# untitled.net
KiCad netlist of a schematic drawn in EAGLE
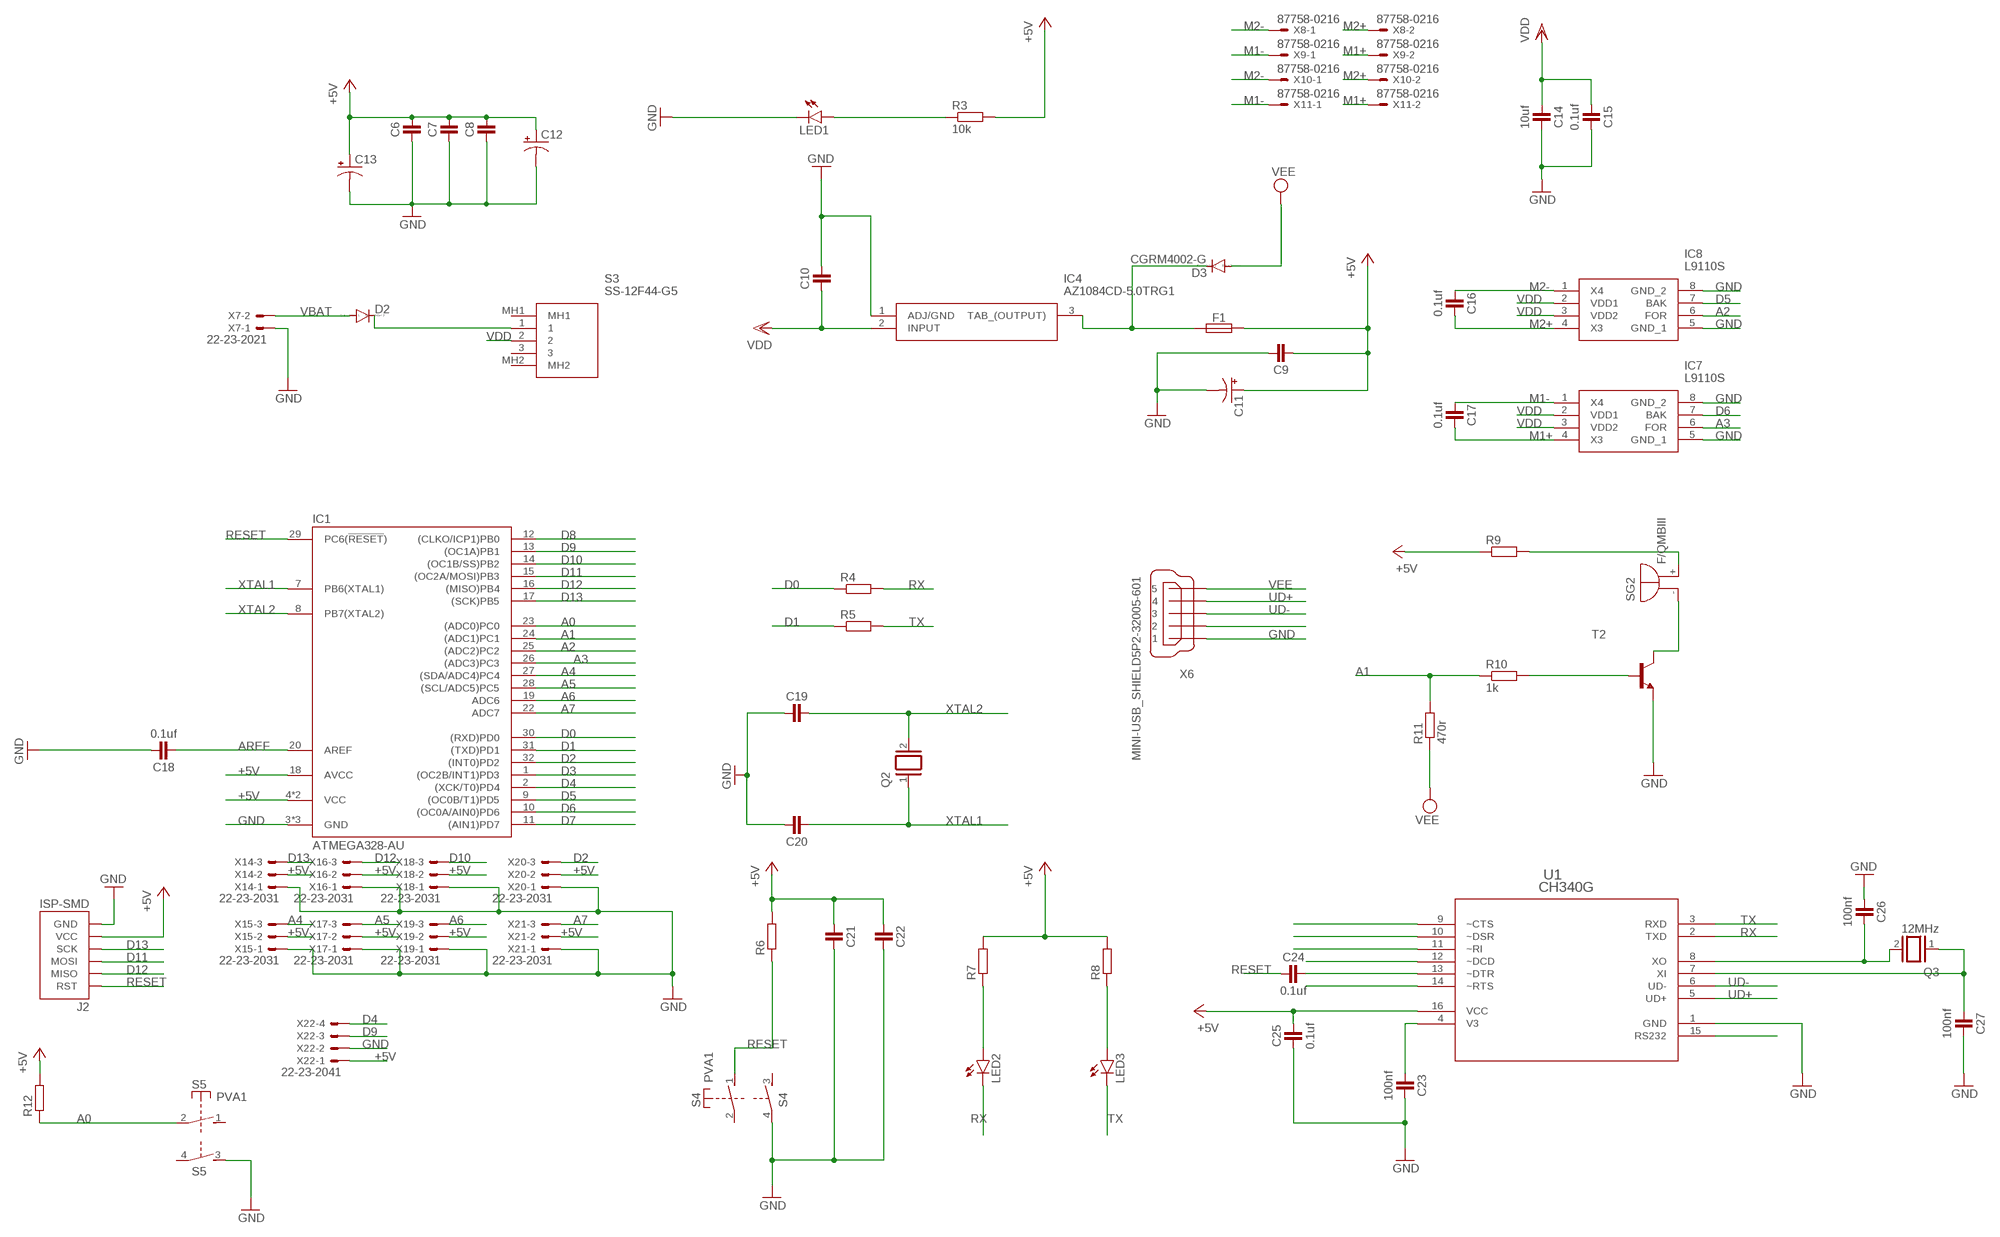
[diagram p0: schematic, sheet 1]

(export (version "E")
  (design (tool "Eeschema 10.0.6"))
  (components
    (comp (ref "C6")
      (value "CAPACITOR-0603")
      (footprint "eagle-import:C0603")
      (libsource (lib "eagle-import") (part "CAPACITOR-0603"))
    )
    (comp (ref "C7")
      (value "CAPACITOR-0603")
      (footprint "eagle-import:C0603")
      (libsource (lib "eagle-import") (part "CAPACITOR-0603"))
    )
    (comp (ref "C8")
      (value "CAPACITOR-0603")
      (footprint "eagle-import:C0603")
      (libsource (lib "eagle-import") (part "CAPACITOR-0603"))
    )
    (comp (ref "C9")
      (value "CAPACITOR-0603")
      (footprint "eagle-import:C0603")
      (libsource (lib "eagle-import") (part "CAPACITOR-0603"))
    )
    (comp (ref "C10")
      (value "CAPACITOR-0603")
      (footprint "eagle-import:C0603")
      (libsource (lib "eagle-import") (part "CAPACITOR-0603"))
    )
    (comp (ref "C11")
      (value "CPOL-USB/3528-21R")
      (footprint "eagle-import:B_3528-21R")
      (libsource (lib "eagle-import") (part "CPOL-USB/3528-21R"))
    )
    (comp (ref "C12")
      (value "CPOL-USB/3528-21R")
      (footprint "eagle-import:B_3528-21R")
      (libsource (lib "eagle-import") (part "CPOL-USB/3528-21R"))
    )
    (comp (ref "C13")
      (value "CPOL-USB/3528-21R")
      (footprint "eagle-import:B_3528-21R")
      (libsource (lib "eagle-import") (part "CPOL-USB/3528-21R"))
    )
    (comp (ref "C14")
      (value "10uf")
      (footprint "eagle-import:C0603")
      (libsource (lib "eagle-import") (part "CAPACITOR-0603"))
    )
    (comp (ref "C15")
      (value "0.1uf")
      (footprint "eagle-import:C0603")
      (libsource (lib "eagle-import") (part "CAPACITOR-0603"))
    )
    (comp (ref "C16")
      (value "0.1uf")
      (footprint "eagle-import:C0603")
      (libsource (lib "eagle-import") (part "CAPACITOR-0603"))
    )
    (comp (ref "C17")
      (value "0.1uf")
      (footprint "eagle-import:C0603")
      (libsource (lib "eagle-import") (part "CAPACITOR-0603"))
    )
    (comp (ref "C18")
      (value "0.1uf")
      (footprint "eagle-import:C0603")
      (libsource (lib "eagle-import") (part "CAPACITOR-0603"))
    )
    (comp (ref "C19")
      (value "CAPACITOR-0603")
      (footprint "eagle-import:C0603")
      (libsource (lib "eagle-import") (part "CAPACITOR-0603"))
    )
    (comp (ref "C20")
      (value "CAPACITOR-0603")
      (footprint "eagle-import:C0603")
      (libsource (lib "eagle-import") (part "CAPACITOR-0603"))
    )
    (comp (ref "C21")
      (value "CAPACITOR-0603")
      (footprint "eagle-import:C0603")
      (libsource (lib "eagle-import") (part "CAPACITOR-0603"))
    )
    (comp (ref "C22")
      (value "CAPACITOR-0603")
      (footprint "eagle-import:C0603")
      (libsource (lib "eagle-import") (part "CAPACITOR-0603"))
    )
    (comp (ref "C23")
      (value "100nf")
      (footprint "eagle-import:C0603")
      (libsource (lib "eagle-import") (part "CAPACITOR-0603"))
    )
    (comp (ref "C24")
      (value "0.1uf")
      (footprint "eagle-import:C0603")
      (libsource (lib "eagle-import") (part "CAPACITOR-0603"))
    )
    (comp (ref "C25")
      (value "0.1uf")
      (footprint "eagle-import:C0603")
      (libsource (lib "eagle-import") (part "CAPACITOR-0603"))
    )
    (comp (ref "C26")
      (value "100nf")
      (footprint "eagle-import:C0603")
      (libsource (lib "eagle-import") (part "CAPACITOR-0603"))
    )
    (comp (ref "C27")
      (value "100nf")
      (footprint "eagle-import:C0603")
      (libsource (lib "eagle-import") (part "CAPACITOR-0603"))
    )
    (comp (ref "D2")
      (value "DIODE-DO-214AC")
      (footprint "eagle-import:DO-214AC")
      (libsource (lib "eagle-import") (part "DIODE-DO-214AC"))
    )
    (comp (ref "D3")
      (value "CGRM4002-G")
      (footprint "eagle-import:SOD-123_MINI-SMA")
      (libsource (lib "eagle-import") (part "CGRM400-G2"))
    )
    (comp (ref "F1")
      (value "FUSE-1812")
      (footprint "eagle-import:C1812")
      (libsource (lib "eagle-import") (part "FUSE-1812"))
    )
    (comp (ref "IC1")
      (value "ATMEGA328-AU")
      (footprint "eagle-import:TQFP32")
      (libsource (lib "eagle-import") (part "ATMEGA328-AU"))
    )
    (comp (ref "IC4")
      (value "AZ1084CD-5.0TRG1")
      (footprint "eagle-import:TO-252_1")
      (fields (field (name "MOUSER_PART_NUMBER") "621-AZ1084CD-5.0TRG1"))
      (libsource (lib "eagle-import") (part "AZ1084CD-5.0TRG1"))
    )
    (comp (ref "IC7")
      (value "L9110S")
      (footprint "eagle-import:SOIC127P600X175-8N")
      (libsource (lib "eagle-import") (part "L9110S"))
    )
    (comp (ref "IC8")
      (value "L9110S")
      (footprint "eagle-import:SOIC127P600X175-8N")
      (libsource (lib "eagle-import") (part "L9110S"))
    )
    (comp (ref "J2")
      (value "ISP-SMD")
      (footprint "eagle-import:ISP-2X3_SMD")
      (libsource (lib "eagle-import") (part "ISP-SMD"))
    )
    (comp (ref "LED1")
      (value "LEDCHIPLED_0805")
      (footprint "eagle-import:CHIPLED_0805")
      (libsource (lib "eagle-import") (part "LEDCHIPLED_0805"))
    )
    (comp (ref "LED2")
      (value "LEDCHIPLED_0805")
      (footprint "eagle-import:CHIPLED_0805")
      (libsource (lib "eagle-import") (part "LEDCHIPLED_0805"))
    )
    (comp (ref "LED3")
      (value "LEDCHIPLED_0805")
      (footprint "eagle-import:CHIPLED_0805")
      (libsource (lib "eagle-import") (part "LEDCHIPLED_0805"))
    )
    (comp (ref "Q2")
      (value "XTAL/S")
      (footprint "eagle-import:QS")
      (libsource (lib "eagle-import") (part "XTAL/S"))
    )
    (comp (ref "Q3")
      (value "12MHz")
      (footprint "eagle-import:QS")
      (libsource (lib "eagle-import") (part "XTAL/S"))
    )
    (comp (ref "R3")
      (value "10k")
      (footprint "eagle-import:R0603")
      (libsource (lib "eagle-import") (part "R-EU_R0603"))
    )
    (comp (ref "R4")
      (value "R-EU_R0603")
      (footprint "eagle-import:R0603")
      (libsource (lib "eagle-import") (part "R-EU_R0603"))
    )
    (comp (ref "R5")
      (value "R-EU_R0603")
      (footprint "eagle-import:R0603")
      (libsource (lib "eagle-import") (part "R-EU_R0603"))
    )
    (comp (ref "R6")
      (value "R-EU_R0603")
      (footprint "eagle-import:R0603")
      (libsource (lib "eagle-import") (part "R-EU_R0603"))
    )
    (comp (ref "R7")
      (value "R-EU_R0603")
      (footprint "eagle-import:R0603")
      (libsource (lib "eagle-import") (part "R-EU_R0603"))
    )
    (comp (ref "R8")
      (value "R-EU_R0603")
      (footprint "eagle-import:R0603")
      (libsource (lib "eagle-import") (part "R-EU_R0603"))
    )
    (comp (ref "R9")
      (value "R-EU_R0603")
      (footprint "eagle-import:R0603")
      (libsource (lib "eagle-import") (part "R-EU_R0603"))
    )
    (comp (ref "R10")
      (value "1k")
      (footprint "eagle-import:R0603")
      (libsource (lib "eagle-import") (part "R-EU_R0603"))
    )
    (comp (ref "R11")
      (value "470r")
      (footprint "eagle-import:R0603")
      (libsource (lib "eagle-import") (part "R-EU_R0603"))
    )
    (comp (ref "R12")
      (value "R-EU_R0603")
      (footprint "eagle-import:R0603")
      (libsource (lib "eagle-import") (part "R-EU_R0603"))
    )
    (comp (ref "S3")
      (value "SS-12F44-G5")
      (footprint "eagle-import:SS12F44G5")
      (libsource (lib "eagle-import") (part "SS-12F44-G5"))
    )
    (comp (ref "S4")
      (value "PVA1")
      (footprint "eagle-import:PVA1F")
      (libsource (lib "eagle-import") (part "PVA1"))
    )
    (comp (ref "S5")
      (value "PVA1")
      (footprint "eagle-import:PVA1F")
      (libsource (lib "eagle-import") (part "PVA1"))
    )
    (comp (ref "SG2")
      (value "F/QMBIII")
      (footprint "eagle-import:F_QMBIII")
      (libsource (lib "eagle-import") (part "F/QMBIII"))
    )
    (comp (ref "T2")
      (value "BC817-NPN-SOT23-BEC")
      (footprint "eagle-import:SOT23-BEC")
      (libsource (lib "eagle-import") (part "-NPN-SOT23-BECBC817"))
    )
    (comp (ref "U1")
      (value "CH340G")
      (footprint "eagle-import:SOP16-50-062A")
      (fields (field (name "DESIGNER") "CHIPHOME"))
      (libsource (lib "eagle-import") (part "CH340G"))
    )
    (comp (ref "X6")
      (value "MINI-USB_SHIELD5P2-32005-601")
      (footprint "eagle-import:32005-601")
      (libsource (lib "eagle-import") (part "MINI-USB_SHIELD5P2-32005-601"))
    )
    (comp (ref "X7")
      (value "22-23-2021")
      (footprint "eagle-import:22-23-2021")
      (fields (field (name "MF") "MOLEX"))
      (libsource (lib "eagle-import") (part "22-23-2021"))
    )
    (comp (ref "X8")
      (value "87758-0216")
      (footprint "eagle-import:87758-0216")
      (fields (field (name "MF") "MOLEX"))
      (libsource (lib "eagle-import") (part "87758-0216"))
    )
    (comp (ref "X9")
      (value "87758-0216")
      (footprint "eagle-import:87758-0216")
      (fields (field (name "MF") "MOLEX"))
      (libsource (lib "eagle-import") (part "87758-0216"))
    )
    (comp (ref "X10")
      (value "87758-0216")
      (footprint "eagle-import:87758-0216")
      (fields (field (name "MF") "MOLEX"))
      (libsource (lib "eagle-import") (part "87758-0216"))
    )
    (comp (ref "X11")
      (value "87758-0216")
      (footprint "eagle-import:87758-0216")
      (fields (field (name "MF") "MOLEX"))
      (libsource (lib "eagle-import") (part "87758-0216"))
    )
    (comp (ref "X14")
      (value "22-23-2031")
      (footprint "eagle-import:22-23-2031")
      (fields (field (name "MF") "MOLEX"))
      (libsource (lib "eagle-import") (part "22-23-2031"))
    )
    (comp (ref "X15")
      (value "22-23-2031")
      (footprint "eagle-import:22-23-2031")
      (fields (field (name "MF") "MOLEX"))
      (libsource (lib "eagle-import") (part "22-23-2031"))
    )
    (comp (ref "X16")
      (value "22-23-2031")
      (footprint "eagle-import:22-23-2031")
      (fields (field (name "MF") "MOLEX"))
      (libsource (lib "eagle-import") (part "22-23-2031"))
    )
    (comp (ref "X17")
      (value "22-23-2031")
      (footprint "eagle-import:22-23-2031")
      (fields (field (name "MF") "MOLEX"))
      (libsource (lib "eagle-import") (part "22-23-2031"))
    )
    (comp (ref "X18")
      (value "22-23-2031")
      (footprint "eagle-import:22-23-2031")
      (fields (field (name "MF") "MOLEX"))
      (libsource (lib "eagle-import") (part "22-23-2031"))
    )
    (comp (ref "X19")
      (value "22-23-2031")
      (footprint "eagle-import:22-23-2031")
      (fields (field (name "MF") "MOLEX"))
      (libsource (lib "eagle-import") (part "22-23-2031"))
    )
    (comp (ref "X20")
      (value "22-23-2031")
      (footprint "eagle-import:22-23-2031")
      (fields (field (name "MF") "MOLEX"))
      (libsource (lib "eagle-import") (part "22-23-2031"))
    )
    (comp (ref "X21")
      (value "22-23-2031")
      (footprint "eagle-import:22-23-2031")
      (fields (field (name "MF") "MOLEX"))
      (libsource (lib "eagle-import") (part "22-23-2031"))
    )
    (comp (ref "X22")
      (value "22-23-2041")
      (footprint "eagle-import:22-23-2041")
      (fields (field (name "MF") "MOLEX"))
      (libsource (lib "eagle-import") (part "22-23-2041"))
    )
  )
  (nets
    (net (code "1") (name "+5V") (class "Default")
      (node (ref "C11") (pin "+") (pinfunction "+_+") (pintype "passive"))
      (node (ref "C12") (pin "+") (pinfunction "+_+") (pintype "passive"))
      (node (ref "C13") (pin "+") (pinfunction "+_+") (pintype "passive"))
      (node (ref "C21") (pin "1") (pinfunction "1_1") (pintype "passive"))
      (node (ref "C22") (pin "1") (pinfunction "1_1") (pintype "passive"))
      (node (ref "C25") (pin "2") (pinfunction "2_2") (pintype "passive"))
      (node (ref "C6") (pin "2") (pinfunction "2_2") (pintype "passive"))
      (node (ref "C7") (pin "2") (pinfunction "2_2") (pintype "passive"))
      (node (ref "C8") (pin "2") (pinfunction "2_2") (pintype "passive"))
      (node (ref "C9") (pin "1") (pinfunction "1_1") (pintype "passive"))
      (node (ref "F1") (pin "2") (pinfunction "2_2") (pintype "passive"))
      (node (ref "IC1") (pin "18") (pinfunction "AVCC_18") (pintype "power_in"))
      (node (ref "IC1") (pin "4") (pinfunction "VCC_4") (pintype "power_in"))
      (node (ref "IC1") (pin "6") (pinfunction "VCC_6") (pintype "power_in"))
      (node (ref "J2") (pin "VCC") (pinfunction "VCC_VCC") (pintype "power_in"))
      (node (ref "R12") (pin "2") (pinfunction "2_2") (pintype "passive"))
      (node (ref "R3") (pin "2") (pinfunction "2_2") (pintype "passive"))
      (node (ref "R6") (pin "2") (pinfunction "2_2") (pintype "passive"))
      (node (ref "R7") (pin "2") (pinfunction "2_2") (pintype "passive"))
      (node (ref "R8") (pin "2") (pinfunction "2_2") (pintype "passive"))
      (node (ref "R9") (pin "1") (pinfunction "1_1") (pintype "passive"))
      (node (ref "U1") (pin "16") (pinfunction "VCC_16") (pintype "passive"))
      (node (ref "X14") (pin "2") (pinfunction "S_2") (pintype "passive"))
      (node (ref "X15") (pin "2") (pinfunction "S_2") (pintype "passive"))
      (node (ref "X16") (pin "2") (pinfunction "S_2") (pintype "passive"))
      (node (ref "X17") (pin "2") (pinfunction "S_2") (pintype "passive"))
      (node (ref "X18") (pin "2") (pinfunction "S_2") (pintype "passive"))
      (node (ref "X19") (pin "2") (pinfunction "S_2") (pintype "passive"))
      (node (ref "X20") (pin "2") (pinfunction "S_2") (pintype "passive"))
      (node (ref "X21") (pin "2") (pinfunction "S_2") (pintype "passive"))
      (node (ref "X22") (pin "1") (pinfunction "S_1") (pintype "passive"))
    )
    (net (code "2") (name "/A0") (class "Default")
      (node (ref "IC1") (pin "23") (pinfunction "(ADC0)PC0_23") (pintype "bidirectional"))
      (node (ref "R12") (pin "1") (pinfunction "1_1") (pintype "passive"))
      (node (ref "S5") (pin "2") (pinfunction "P_2") (pintype "passive"))
    )
    (net (code "3") (name "/A1") (class "Default")
      (node (ref "IC1") (pin "24") (pinfunction "(ADC1)PC1_24") (pintype "bidirectional"))
      (node (ref "R10") (pin "1") (pinfunction "1_1") (pintype "passive"))
      (node (ref "R11") (pin "2") (pinfunction "2_2") (pintype "passive"))
    )
    (net (code "4") (name "/A2") (class "Default")
      (node (ref "IC1") (pin "25") (pinfunction "(ADC2)PC2_25") (pintype "bidirectional"))
      (node (ref "IC8") (pin "6") (pinfunction "FOR_6") (pintype "bidirectional"))
    )
    (net (code "5") (name "/A3") (class "Default")
      (node (ref "IC1") (pin "26") (pinfunction "(ADC3)PC3_26") (pintype "bidirectional"))
      (node (ref "IC7") (pin "6") (pinfunction "FOR_6") (pintype "bidirectional"))
    )
    (net (code "6") (name "/A4") (class "Default")
      (node (ref "IC1") (pin "27") (pinfunction "(SDA/ADC4)PC4_27") (pintype "bidirectional"))
      (node (ref "X15") (pin "3") (pinfunction "S_3") (pintype "passive"))
    )
    (net (code "7") (name "/A5") (class "Default")
      (node (ref "IC1") (pin "28") (pinfunction "(SCL/ADC5)PC5_28") (pintype "bidirectional"))
      (node (ref "X17") (pin "3") (pinfunction "S_3") (pintype "passive"))
    )
    (net (code "8") (name "/A6") (class "Default")
      (node (ref "IC1") (pin "19") (pinfunction "ADC6_19") (pintype "bidirectional"))
      (node (ref "X19") (pin "3") (pinfunction "S_3") (pintype "passive"))
    )
    (net (code "9") (name "/A7") (class "Default")
      (node (ref "IC1") (pin "22") (pinfunction "ADC7_22") (pintype "bidirectional"))
      (node (ref "X21") (pin "3") (pinfunction "S_3") (pintype "passive"))
    )
    (net (code "10") (name "/AREF") (class "Default")
      (node (ref "C18") (pin "1") (pinfunction "1_1") (pintype "passive"))
      (node (ref "IC1") (pin "20") (pinfunction "AREF_20") (pintype "passive"))
    )
    (net (code "11") (name "/D0") (class "Default")
      (node (ref "IC1") (pin "30") (pinfunction "(RXD)PD0_30") (pintype "bidirectional"))
      (node (ref "R4") (pin "1") (pinfunction "1_1") (pintype "passive"))
    )
    (net (code "12") (name "/D1") (class "Default")
      (node (ref "IC1") (pin "31") (pinfunction "(TXD)PD1_31") (pintype "bidirectional"))
      (node (ref "R5") (pin "1") (pinfunction "1_1") (pintype "passive"))
    )
    (net (code "13") (name "/D2") (class "Default")
      (node (ref "IC1") (pin "32") (pinfunction "(INT0)PD2_32") (pintype "bidirectional"))
      (node (ref "X20") (pin "3") (pinfunction "S_3") (pintype "passive"))
    )
    (net (code "14") (name "/D3") (class "Default")
      (node (ref "IC1") (pin "1") (pinfunction "(OC2B/INT1)PD3_1") (pintype "bidirectional"))
    )
    (net (code "15") (name "/D4") (class "Default")
      (node (ref "IC1") (pin "2") (pinfunction "(XCK/T0)PD4_2") (pintype "bidirectional"))
      (node (ref "X22") (pin "4") (pinfunction "S_4") (pintype "passive"))
    )
    (net (code "16") (name "/D5") (class "Default")
      (node (ref "IC1") (pin "9") (pinfunction "(OC0B/T1)PD5_9") (pintype "bidirectional"))
      (node (ref "IC8") (pin "7") (pinfunction "BAK_7") (pintype "bidirectional"))
    )
    (net (code "17") (name "/D6") (class "Default")
      (node (ref "IC1") (pin "10") (pinfunction "(OC0A/AIN0)PD6_10") (pintype "bidirectional"))
      (node (ref "IC7") (pin "7") (pinfunction "BAK_7") (pintype "bidirectional"))
    )
    (net (code "18") (name "/D7") (class "Default")
      (node (ref "IC1") (pin "11") (pinfunction "(AIN1)PD7_11") (pintype "bidirectional"))
    )
    (net (code "19") (name "/D8") (class "Default")
      (node (ref "IC1") (pin "12") (pinfunction "(CLKO/ICP1)PB0_12") (pintype "bidirectional"))
    )
    (net (code "20") (name "/D9") (class "Default")
      (node (ref "IC1") (pin "13") (pinfunction "(OC1A)PB1_13") (pintype "bidirectional"))
      (node (ref "X22") (pin "3") (pinfunction "S_3") (pintype "passive"))
    )
    (net (code "21") (name "/D10") (class "Default")
      (node (ref "IC1") (pin "14") (pinfunction "(OC1B/SS)PB2_14") (pintype "bidirectional"))
      (node (ref "X18") (pin "3") (pinfunction "S_3") (pintype "passive"))
    )
    (net (code "22") (name "/D11") (class "Default")
      (node (ref "IC1") (pin "15") (pinfunction "(OC2A/MOSI)PB3_15") (pintype "bidirectional"))
      (node (ref "J2") (pin "MOSI") (pinfunction "MOSI_MOSI") (pintype "bidirectional"))
    )
    (net (code "23") (name "/D12") (class "Default")
      (node (ref "IC1") (pin "16") (pinfunction "(MISO)PB4_16") (pintype "bidirectional"))
      (node (ref "J2") (pin "MISO") (pinfunction "MISO_MISO") (pintype "bidirectional"))
      (node (ref "X16") (pin "3") (pinfunction "S_3") (pintype "passive"))
    )
    (net (code "24") (name "/D13") (class "Default")
      (node (ref "IC1") (pin "17") (pinfunction "(SCK)PB5_17") (pintype "bidirectional"))
      (node (ref "J2") (pin "SCK") (pinfunction "SCK_SCK") (pintype "bidirectional"))
      (node (ref "X14") (pin "3") (pinfunction "S_3") (pintype "passive"))
    )
    (net (code "25") (name "/M1+") (class "Default")
      (node (ref "C17") (pin "2") (pinfunction "2_2") (pintype "passive"))
      (node (ref "IC7") (pin "4") (pinfunction "X3_4") (pintype "bidirectional"))
      (node (ref "X11") (pin "2") (pinfunction "S_2") (pintype "passive"))
      (node (ref "X9") (pin "2") (pinfunction "S_2") (pintype "passive"))
    )
    (net (code "26") (name "/M1-") (class "Default")
      (node (ref "C17") (pin "1") (pinfunction "1_1") (pintype "passive"))
      (node (ref "IC7") (pin "1") (pinfunction "X4_1") (pintype "bidirectional"))
      (node (ref "X11") (pin "1") (pinfunction "S_1") (pintype "passive"))
      (node (ref "X9") (pin "1") (pinfunction "S_1") (pintype "passive"))
    )
    (net (code "27") (name "/M2+") (class "Default")
      (node (ref "C16") (pin "2") (pinfunction "2_2") (pintype "passive"))
      (node (ref "IC8") (pin "4") (pinfunction "X3_4") (pintype "bidirectional"))
      (node (ref "X10") (pin "2") (pinfunction "S_2") (pintype "passive"))
      (node (ref "X8") (pin "2") (pinfunction "S_2") (pintype "passive"))
    )
    (net (code "28") (name "/M2-") (class "Default")
      (node (ref "C16") (pin "1") (pinfunction "1_1") (pintype "passive"))
      (node (ref "IC8") (pin "1") (pinfunction "X4_1") (pintype "bidirectional"))
      (node (ref "X10") (pin "1") (pinfunction "S_1") (pintype "passive"))
      (node (ref "X8") (pin "1") (pinfunction "S_1") (pintype "passive"))
    )
    (net (code "29") (name "/RESET") (class "Default")
      (node (ref "C24") (pin "1") (pinfunction "1_1") (pintype "passive"))
      (node (ref "IC1") (pin "29") (pinfunction "PC6(~{RESET})_29") (pintype "bidirectional"))
      (node (ref "J2") (pin "RST") (pinfunction "RST_RST") (pintype "bidirectional"))
      (node (ref "R6") (pin "1") (pinfunction "1_1") (pintype "passive"))
      (node (ref "S4") (pin "1") (pinfunction "S_1") (pintype "passive"))
    )
    (net (code "30") (name "/RX") (class "Default")
      (node (ref "LED2") (pin "C") (pinfunction "C_C") (pintype "passive"))
      (node (ref "R4") (pin "2") (pinfunction "2_2") (pintype "passive"))
      (node (ref "U1") (pin "2") (pinfunction "TXD_2") (pintype "passive"))
    )
    (net (code "31") (name "/TX") (class "Default")
      (node (ref "LED3") (pin "C") (pinfunction "C_C") (pintype "passive"))
      (node (ref "R5") (pin "2") (pinfunction "2_2") (pintype "passive"))
      (node (ref "U1") (pin "3") (pinfunction "RXD_3") (pintype "passive"))
    )
    (net (code "32") (name "/UD+") (class "Default")
      (node (ref "U1") (pin "5") (pinfunction "UD+_5") (pintype "passive"))
      (node (ref "X6") (pin "4") (pinfunction "4_4") (pintype "passive"))
    )
    (net (code "33") (name "/UD-") (class "Default")
      (node (ref "U1") (pin "6") (pinfunction "UD-_6") (pintype "passive"))
      (node (ref "X6") (pin "3") (pinfunction "3_3") (pintype "passive"))
    )
    (net (code "34") (name "/VBAT") (class "Default")
      (node (ref "D2") (pin "A") (pinfunction "A_A") (pintype "passive"))
      (node (ref "X7") (pin "2") (pinfunction "S_2") (pintype "passive"))
    )
    (net (code "35") (name "/XTAL1") (class "Default")
      (node (ref "C20") (pin "1") (pinfunction "1_1") (pintype "passive"))
      (node (ref "IC1") (pin "7") (pinfunction "PB6(XTAL1)_7") (pintype "bidirectional"))
      (node (ref "Q2") (pin "1") (pinfunction "1_1") (pintype "passive"))
    )
    (net (code "36") (name "/XTAL2") (class "Default")
      (node (ref "C19") (pin "2") (pinfunction "2_2") (pintype "passive"))
      (node (ref "IC1") (pin "8") (pinfunction "PB7(XTAL2)_8") (pintype "bidirectional"))
      (node (ref "Q2") (pin "2") (pinfunction "2_2") (pintype "passive"))
    )
    (net (code "37") (name "GND") (class "Default")
      (node (ref "C10") (pin "2") (pinfunction "2_2") (pintype "passive"))
      (node (ref "C11") (pin "-") (pinfunction "-_-") (pintype "passive"))
      (node (ref "C12") (pin "-") (pinfunction "-_-") (pintype "passive"))
      (node (ref "C13") (pin "-") (pinfunction "-_-") (pintype "passive"))
      (node (ref "C14") (pin "2") (pinfunction "2_2") (pintype "passive"))
      (node (ref "C15") (pin "2") (pinfunction "2_2") (pintype "passive"))
      (node (ref "C18") (pin "2") (pinfunction "2_2") (pintype "passive"))
      (node (ref "C19") (pin "1") (pinfunction "1_1") (pintype "passive"))
      (node (ref "C20") (pin "2") (pinfunction "2_2") (pintype "passive"))
      (node (ref "C21") (pin "2") (pinfunction "2_2") (pintype "passive"))
      (node (ref "C22") (pin "2") (pinfunction "2_2") (pintype "passive"))
      (node (ref "C23") (pin "2") (pinfunction "2_2") (pintype "passive"))
      (node (ref "C25") (pin "1") (pinfunction "1_1") (pintype "passive"))
      (node (ref "C26") (pin "1") (pinfunction "1_1") (pintype "passive"))
      (node (ref "C27") (pin "2") (pinfunction "2_2") (pintype "passive"))
      (node (ref "C6") (pin "1") (pinfunction "1_1") (pintype "passive"))
      (node (ref "C7") (pin "1") (pinfunction "1_1") (pintype "passive"))
      (node (ref "C8") (pin "1") (pinfunction "1_1") (pintype "passive"))
      (node (ref "C9") (pin "2") (pinfunction "2_2") (pintype "passive"))
      (node (ref "IC1") (pin "21") (pinfunction "GND_21") (pintype "power_in"))
      (node (ref "IC1") (pin "3") (pinfunction "GND_3") (pintype "power_in"))
      (node (ref "IC1") (pin "5") (pinfunction "GND_5") (pintype "power_in"))
      (node (ref "IC4") (pin "1") (pinfunction "ADJ/GND_1") (pintype "bidirectional"))
      (node (ref "IC7") (pin "5") (pinfunction "GND_1_5") (pintype "bidirectional"))
      (node (ref "IC7") (pin "8") (pinfunction "GND_2_8") (pintype "bidirectional"))
      (node (ref "IC8") (pin "5") (pinfunction "GND_1_5") (pintype "bidirectional"))
      (node (ref "IC8") (pin "8") (pinfunction "GND_2_8") (pintype "bidirectional"))
      (node (ref "J2") (pin "GND") (pinfunction "GND_GND") (pintype "power_in"))
      (node (ref "LED1") (pin "C") (pinfunction "C_C") (pintype "passive"))
      (node (ref "S4") (pin "4") (pinfunction "P_4") (pintype "passive"))
      (node (ref "S5") (pin "3") (pinfunction "S_3") (pintype "passive"))
      (node (ref "T2") (pin "E") (pinfunction "E_E") (pintype "passive"))
      (node (ref "U1") (pin "1") (pinfunction "GND_1") (pintype "passive"))
      (node (ref "X14") (pin "1") (pinfunction "S_1") (pintype "passive"))
      (node (ref "X15") (pin "1") (pinfunction "S_1") (pintype "passive"))
      (node (ref "X16") (pin "1") (pinfunction "S_1") (pintype "passive"))
      (node (ref "X17") (pin "1") (pinfunction "S_1") (pintype "passive"))
      (node (ref "X18") (pin "1") (pinfunction "S_1") (pintype "passive"))
      (node (ref "X19") (pin "1") (pinfunction "S_1") (pintype "passive"))
      (node (ref "X20") (pin "1") (pinfunction "S_1") (pintype "passive"))
      (node (ref "X21") (pin "1") (pinfunction "S_1") (pintype "passive"))
      (node (ref "X22") (pin "2") (pinfunction "S_2") (pintype "passive"))
      (node (ref "X6") (pin "1") (pinfunction "1_1") (pintype "passive"))
      (node (ref "X7") (pin "1") (pinfunction "S_1") (pintype "passive"))
    )
    (net (code "38") (name "Net-(D2-PadC)") (class "Default")
      (node (ref "D2") (pin "C") (pinfunction "C_C") (pintype "passive"))
      (node (ref "S3") (pin "1") (pinfunction "1_1") (pintype "bidirectional"))
    )
    (net (code "39") (name "Net-(IC4-TAB_(OUTPUT))") (class "Default")
      (node (ref "D3") (pin "C") (pinfunction "C_C") (pintype "passive"))
      (node (ref "F1") (pin "1") (pinfunction "1_1") (pintype "passive"))
      (node (ref "IC4") (pin "3") (pinfunction "TAB_(OUTPUT)_3") (pintype "bidirectional"))
    )
    (net (code "40") (name "Net-(LED1-PadA)") (class "Default")
      (node (ref "LED1") (pin "A") (pinfunction "A_A") (pintype "passive"))
      (node (ref "R3") (pin "1") (pinfunction "1_1") (pintype "passive"))
    )
    (net (code "41") (name "Net-(LED2-PadA)") (class "Default")
      (node (ref "LED2") (pin "A") (pinfunction "A_A") (pintype "passive"))
      (node (ref "R7") (pin "1") (pinfunction "1_1") (pintype "passive"))
    )
    (net (code "42") (name "Net-(LED3-PadA)") (class "Default")
      (node (ref "LED3") (pin "A") (pinfunction "A_A") (pintype "passive"))
      (node (ref "R8") (pin "1") (pinfunction "1_1") (pintype "passive"))
    )
    (net (code "43") (name "Net-(R10-Pad2)") (class "Default")
      (node (ref "R10") (pin "2") (pinfunction "2_2") (pintype "passive"))
      (node (ref "T2") (pin "B") (pinfunction "B_B") (pintype "passive"))
    )
    (net (code "44") (name "Net-(SG2-+)") (class "Default")
      (node (ref "SG2") (pin "-") (pinfunction "+_-") (pintype "passive"))
      (node (ref "T2") (pin "C") (pinfunction "C_C") (pintype "passive"))
    )
    (net (code "45") (name "Net-(SG2--)") (class "Default")
      (node (ref "R9") (pin "2") (pinfunction "2_2") (pintype "passive"))
      (node (ref "SG2") (pin "+") (pinfunction "-_+") (pintype "passive"))
    )
    (net (code "46") (name "Net-(U1-V3)") (class "Default")
      (node (ref "C23") (pin "1") (pinfunction "1_1") (pintype "passive"))
      (node (ref "U1") (pin "4") (pinfunction "V3_4") (pintype "passive"))
    )
    (net (code "47") (name "Net-(U1-XI)") (class "Default")
      (node (ref "C27") (pin "1") (pinfunction "1_1") (pintype "passive"))
      (node (ref "Q3") (pin "1") (pinfunction "1_1") (pintype "passive"))
      (node (ref "U1") (pin "7") (pinfunction "XI_7") (pintype "passive"))
    )
    (net (code "48") (name "Net-(U1-XO)") (class "Default")
      (node (ref "C26") (pin "2") (pinfunction "2_2") (pintype "passive"))
      (node (ref "Q3") (pin "2") (pinfunction "2_2") (pintype "passive"))
      (node (ref "U1") (pin "8") (pinfunction "XO_8") (pintype "passive"))
    )
    (net (code "49") (name "Net-(U1-~{DTR})") (class "Default")
      (node (ref "C24") (pin "2") (pinfunction "2_2") (pintype "passive"))
      (node (ref "U1") (pin "13") (pinfunction "~{DTR}_13") (pintype "passive"))
    )
    (net (code "50") (name "VDD") (class "Default")
      (node (ref "C10") (pin "1") (pinfunction "1_1") (pintype "passive"))
      (node (ref "C14") (pin "1") (pinfunction "1_1") (pintype "passive"))
      (node (ref "C15") (pin "1") (pinfunction "1_1") (pintype "passive"))
      (node (ref "IC4") (pin "2") (pinfunction "INPUT_2") (pintype "bidirectional"))
      (node (ref "IC7") (pin "2") (pinfunction "VDD1_2") (pintype "bidirectional"))
      (node (ref "IC7") (pin "3") (pinfunction "VDD2_3") (pintype "bidirectional"))
      (node (ref "IC8") (pin "2") (pinfunction "VDD1_2") (pintype "bidirectional"))
      (node (ref "IC8") (pin "3") (pinfunction "VDD2_3") (pintype "bidirectional"))
      (node (ref "S3") (pin "2") (pinfunction "2_2") (pintype "bidirectional"))
    )
    (net (code "51") (name "VEE") (class "Default")
      (node (ref "D3") (pin "A") (pinfunction "A_A") (pintype "passive"))
      (node (ref "R11") (pin "1") (pinfunction "1_1") (pintype "passive"))
      (node (ref "X6") (pin "5") (pinfunction "5_5") (pintype "passive"))
    )
    (net (code "52") (name "unconnected-(S3-Pad3)") (class "Default")
      (node (ref "S3") (pin "3") (pinfunction "3_3") (pintype "bidirectional"))
    )
    (net (code "53") (name "unconnected-(S3-PadMH1)") (class "Default")
      (node (ref "S3") (pin "MH1") (pinfunction "MH1_MH1") (pintype "bidirectional"))
    )
    (net (code "54") (name "unconnected-(S3-PadMH2)") (class "Default")
      (node (ref "S3") (pin "MH2") (pinfunction "MH2_MH2") (pintype "bidirectional"))
    )
    (net (code "55") (name "unconnected-(S4A-P-Pad2)") (class "Default")
      (node (ref "S4") (pin "2") (pinfunction "P_2") (pintype "passive"))
    )
    (net (code "56") (name "unconnected-(S4B-S-Pad3)") (class "Default")
      (node (ref "S4") (pin "3") (pinfunction "S_3") (pintype "passive"))
    )
    (net (code "57") (name "unconnected-(S5A-S-Pad1)") (class "Default")
      (node (ref "S5") (pin "1") (pinfunction "S_1") (pintype "passive"))
    )
    (net (code "58") (name "unconnected-(S5B-P-Pad4)") (class "Default")
      (node (ref "S5") (pin "4") (pinfunction "P_4") (pintype "passive"))
    )
    (net (code "59") (name "unconnected-(U1-RS232-Pad15)") (class "Default")
      (node (ref "U1") (pin "15") (pinfunction "RS232_15") (pintype "passive"))
    )
    (net (code "60") (name "unconnected-(U1-~{CTS}-Pad9)") (class "Default")
      (node (ref "U1") (pin "9") (pinfunction "~{CTS}_9") (pintype "passive"))
    )
    (net (code "61") (name "unconnected-(U1-~{DCD}-Pad12)") (class "Default")
      (node (ref "U1") (pin "12") (pinfunction "~{DCD}_12") (pintype "passive"))
    )
    (net (code "62") (name "unconnected-(U1-~{DSR}-Pad10)") (class "Default")
      (node (ref "U1") (pin "10") (pinfunction "~{DSR}_10") (pintype "passive"))
    )
    (net (code "63") (name "unconnected-(U1-~{RI}-Pad11)") (class "Default")
      (node (ref "U1") (pin "11") (pinfunction "~{RI}_11") (pintype "passive"))
    )
    (net (code "64") (name "unconnected-(U1-~{RTS}-Pad14)") (class "Default")
      (node (ref "U1") (pin "14") (pinfunction "~{RTS}_14") (pintype "passive"))
    )
    (net (code "65") (name "unconnected-(X6-Pad2)") (class "Default")
      (node (ref "X6") (pin "2") (pinfunction "2_2") (pintype "passive"))
    )
  )
)
